# 03_Module.net
KiCad netlist of a schematic drawn in Altium Designer
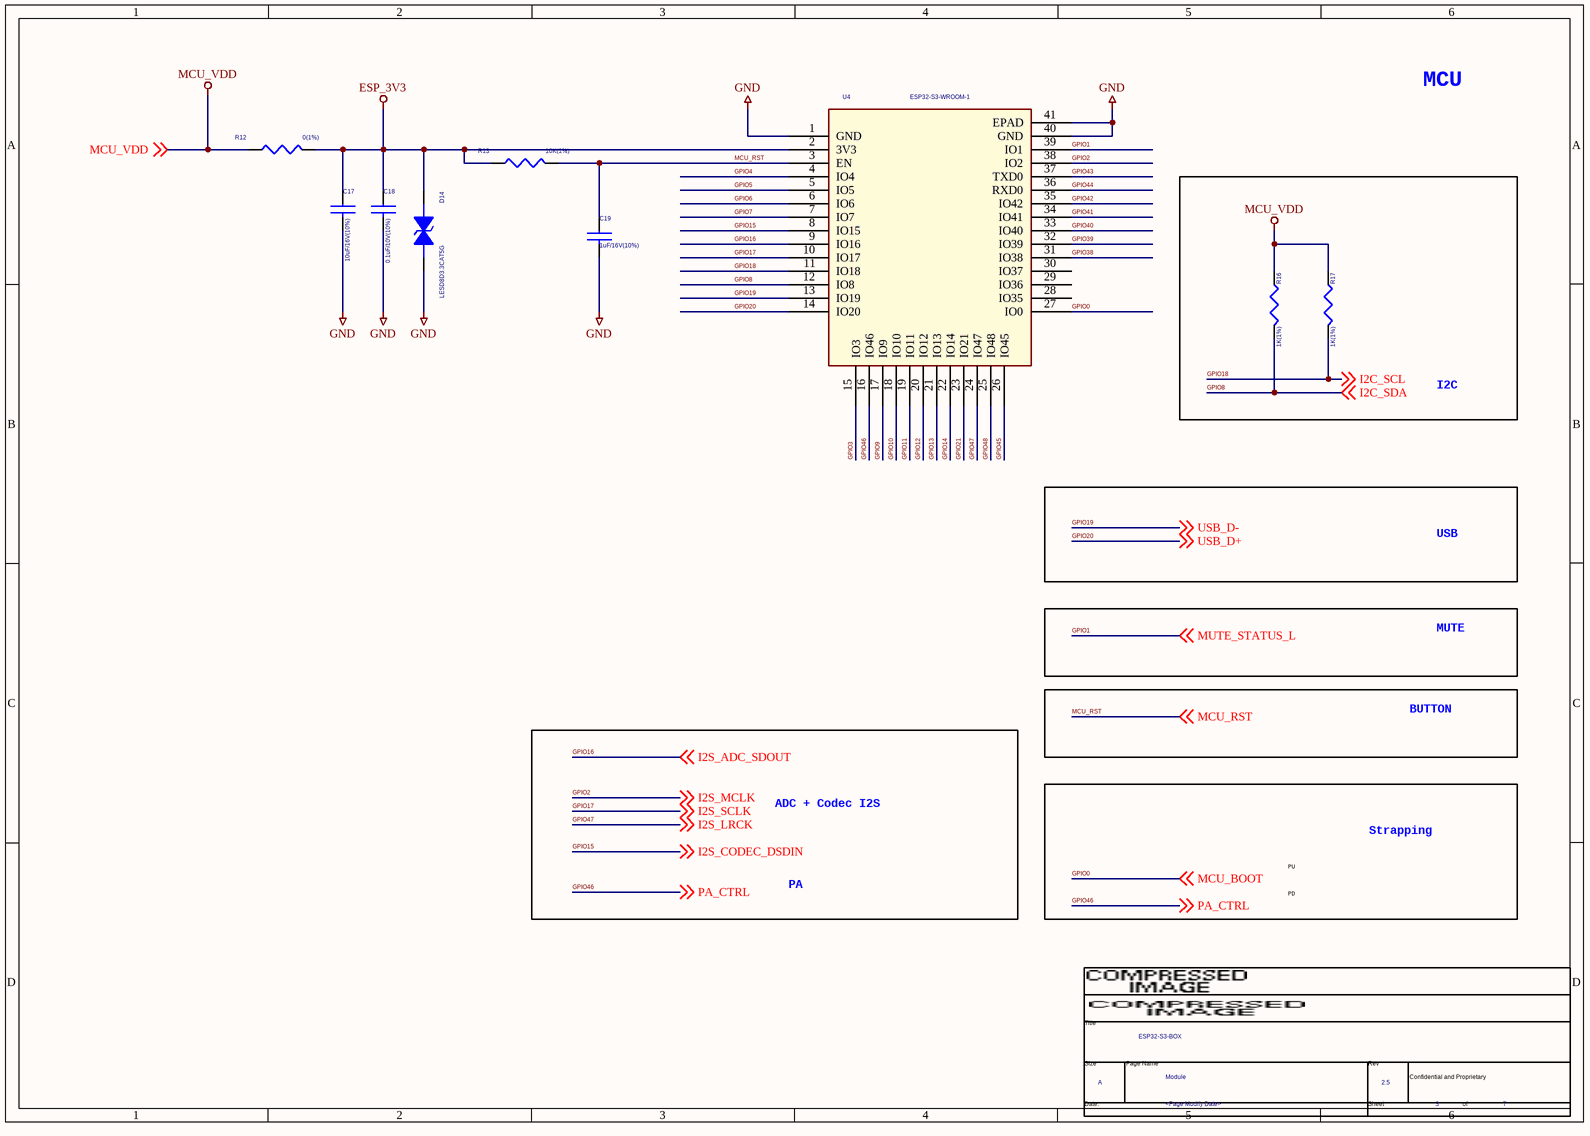
[diagram p0: 03_Module.SchDoc]

(export (version "E")
  (design (tool "Eeschema 10.0.6"))
  (components
    (comp (ref "C17")
      (value "10uF/16V(10%)")
      (footprint "C0603")
      (fields (field (name "PART NUMBER") "ES11067104600000"))
      (libsource (lib "*") (part "CAPACITOR"))
    )
    (comp (ref "C18")
      (value "0.1uF/10V(10%)")
      (footprint "C0402")
      (fields (field (name "PART NUMBER") "ES11045103620000"))
      (libsource (lib "*") (part "CAPACITOR"))
    )
    (comp (ref "C19")
      (value "1uF/16V(10%)")
      (footprint "C0402")
      (fields (field (name "PART NUMBER") "ES11046104610000"))
      (libsource (lib "*") (part "CAPACITOR"))
    )
    (comp (ref "D14")
      (value "LESD8D3.3CAT5G")
      (footprint "SOD882")
      (fields (field (name "PART NUMBER") "ES31320010000000"))
      (libsource (lib "*") (part "DIODE_BI_DIR"))
    )
    (comp (ref "R12")
      (value "0(1%)")
      (footprint "R0603")
      (fields (field (name "PART NUMBER") "ES21060000000001"))
      (libsource (lib "*") (part "RESISTOR"))
    )
    (comp (ref "R13")
      (value "10K(1%)")
      (footprint "R0402")
      (fields (field (name "PART NUMBER") "ES21044100000001"))
      (libsource (lib "*") (part "RESISTOR"))
    )
    (comp (ref "R16")
      (value "1K(1%)")
      (footprint "R0201")
      (fields (field (name "PART NUMBER") "ES21023100000001"))
      (libsource (lib "*") (part "RESISTOR"))
    )
    (comp (ref "R17")
      (value "1K(1%)")
      (footprint "R0201")
      (fields (field (name "PART NUMBER") "ES21023100000001"))
      (libsource (lib "*") (part "RESISTOR"))
    )
    (comp (ref "U4")
      (value "ESP32-S3-WROOM-1")
      (footprint "ESP32-S3-WROOM")
      (libsource (lib "*") (part "ESP32-S3-WROOM"))
    )
  )
  (nets
    (net (code "1") (name "/GPIO3") (class "Default")
      (node (ref "U4") (pin "15") (pinfunction "IO3_15") (pintype "passive"))
    )
    (net (code "2") (name "/GPIO4") (class "Default")
      (node (ref "U4") (pin "4") (pinfunction "IO4_4") (pintype "passive"))
    )
    (net (code "3") (name "/GPIO5") (class "Default")
      (node (ref "U4") (pin "5") (pinfunction "IO5_5") (pintype "passive"))
    )
    (net (code "4") (name "/GPIO6") (class "Default")
      (node (ref "U4") (pin "6") (pinfunction "IO6_6") (pintype "passive"))
    )
    (net (code "5") (name "/GPIO7") (class "Default")
      (node (ref "U4") (pin "7") (pinfunction "IO7_7") (pintype "passive"))
    )
    (net (code "6") (name "/GPIO9") (class "Default")
      (node (ref "U4") (pin "17") (pinfunction "IO9_17") (pintype "passive"))
    )
    (net (code "7") (name "/GPIO10") (class "Default")
      (node (ref "U4") (pin "18") (pinfunction "IO10_18") (pintype "passive"))
    )
    (net (code "8") (name "/GPIO11") (class "Default")
      (node (ref "U4") (pin "19") (pinfunction "IO11_19") (pintype "passive"))
    )
    (net (code "9") (name "/GPIO12") (class "Default")
      (node (ref "U4") (pin "20") (pinfunction "IO12_20") (pintype "passive"))
    )
    (net (code "10") (name "/GPIO13") (class "Default")
      (node (ref "U4") (pin "21") (pinfunction "IO13_21") (pintype "passive"))
    )
    (net (code "11") (name "/GPIO14") (class "Default")
      (node (ref "U4") (pin "22") (pinfunction "IO14_22") (pintype "passive"))
    )
    (net (code "12") (name "/GPIO21") (class "Default")
      (node (ref "U4") (pin "23") (pinfunction "IO21_23") (pintype "passive"))
    )
    (net (code "13") (name "/GPIO38") (class "Default")
      (node (ref "U4") (pin "31") (pinfunction "IO38_31") (pintype "passive"))
    )
    (net (code "14") (name "/GPIO39") (class "Default")
      (node (ref "U4") (pin "32") (pinfunction "IO39_32") (pintype "passive"))
    )
    (net (code "15") (name "/GPIO40") (class "Default")
      (node (ref "U4") (pin "33") (pinfunction "IO40_33") (pintype "passive"))
    )
    (net (code "16") (name "/GPIO41") (class "Default")
      (node (ref "U4") (pin "34") (pinfunction "IO41_34") (pintype "passive"))
    )
    (net (code "17") (name "/GPIO42") (class "Default")
      (node (ref "U4") (pin "35") (pinfunction "IO42_35") (pintype "passive"))
    )
    (net (code "18") (name "/GPIO43") (class "Default")
      (node (ref "U4") (pin "37") (pinfunction "TXD0_37") (pintype "passive"))
    )
    (net (code "19") (name "/GPIO44") (class "Default")
      (node (ref "U4") (pin "36") (pinfunction "RXD0_36") (pintype "passive"))
    )
    (net (code "20") (name "/GPIO45") (class "Default")
      (node (ref "U4") (pin "26") (pinfunction "IO45_26") (pintype "passive"))
    )
    (net (code "21") (name "/GPIO48") (class "Default")
      (node (ref "U4") (pin "25") (pinfunction "IO48_25") (pintype "passive"))
    )
    (net (code "22") (name "ESP_3V3") (class "Default")
      (node (ref "C17") (pin "1") (pinfunction "1_1") (pintype "passive"))
      (node (ref "C18") (pin "1") (pinfunction "1_1") (pintype "passive"))
      (node (ref "D14") (pin "2") (pinfunction "2_2") (pintype "passive"))
      (node (ref "R12") (pin "2") (pinfunction "2_2") (pintype "passive"))
      (node (ref "R13") (pin "1") (pinfunction "1_1") (pintype "passive"))
      (node (ref "U4") (pin "2") (pinfunction "3V3_2") (pintype "power_in"))
    )
    (net (code "23") (name "GND") (class "Default")
      (node (ref "C17") (pin "2") (pinfunction "2_2") (pintype "passive"))
      (node (ref "C18") (pin "2") (pinfunction "2_2") (pintype "passive"))
      (node (ref "C19") (pin "2") (pinfunction "2_2") (pintype "passive"))
      (node (ref "D14") (pin "1") (pinfunction "1_1") (pintype "passive"))
      (node (ref "U4") (pin "1") (pinfunction "GND_1") (pintype "power_in"))
      (node (ref "U4") (pin "40") (pinfunction "GND_40") (pintype "power_in"))
      (node (ref "U4") (pin "41") (pinfunction "EPAD_41") (pintype "power_in"))
    )
    (net (code "24") (name "I2C_SCL") (class "Default")
      (node (ref "R17") (pin "2") (pinfunction "2_2") (pintype "passive"))
      (node (ref "U4") (pin "11") (pinfunction "IO18_11") (pintype "passive"))
    )
    (net (code "25") (name "I2C_SDA") (class "Default")
      (node (ref "R16") (pin "2") (pinfunction "2_2") (pintype "passive"))
      (node (ref "U4") (pin "12") (pinfunction "IO8_12") (pintype "passive"))
    )
    (net (code "26") (name "I2S_ADC_SDOUT") (class "Default")
      (node (ref "U4") (pin "9") (pinfunction "IO16_9") (pintype "passive"))
    )
    (net (code "27") (name "I2S_CODEC_DSDIN") (class "Default")
      (node (ref "U4") (pin "8") (pinfunction "IO15_8") (pintype "passive"))
    )
    (net (code "28") (name "I2S_LRCK") (class "Default")
      (node (ref "U4") (pin "24") (pinfunction "IO47_24") (pintype "passive"))
    )
    (net (code "29") (name "I2S_MCLK") (class "Default")
      (node (ref "U4") (pin "38") (pinfunction "IO2_38") (pintype "passive"))
    )
    (net (code "30") (name "I2S_SCLK") (class "Default")
      (node (ref "U4") (pin "10") (pinfunction "IO17_10") (pintype "passive"))
    )
    (net (code "31") (name "MCU_BOOT") (class "Default")
      (node (ref "U4") (pin "27") (pinfunction "IO0_27") (pintype "passive"))
    )
    (net (code "32") (name "MCU_RST") (class "Default")
      (node (ref "C19") (pin "1") (pinfunction "1_1") (pintype "passive"))
      (node (ref "R13") (pin "2") (pinfunction "2_2") (pintype "passive"))
      (node (ref "U4") (pin "3") (pinfunction "EN_3") (pintype "passive"))
    )
    (net (code "33") (name "MCU_VDD") (class "Default")
      (node (ref "R12") (pin "1") (pinfunction "1_1") (pintype "passive"))
      (node (ref "R16") (pin "1") (pinfunction "1_1") (pintype "passive"))
      (node (ref "R17") (pin "1") (pinfunction "1_1") (pintype "passive"))
    )
    (net (code "34") (name "MUTE_STATUS_L") (class "Default")
      (node (ref "U4") (pin "39") (pinfunction "IO1_39") (pintype "passive"))
    )
    (net (code "35") (name "PA_CTRL") (class "Default")
      (node (ref "U4") (pin "16") (pinfunction "IO46_16") (pintype "passive"))
    )
    (net (code "36") (name "USB_D+") (class "Default")
      (node (ref "U4") (pin "14") (pinfunction "IO20_14") (pintype "passive"))
    )
    (net (code "37") (name "USB_D-") (class "Default")
      (node (ref "U4") (pin "13") (pinfunction "IO19_13") (pintype "passive"))
    )
    (net (code "38") (name "unconnected-(U4-IO35-Pad28)") (class "Default")
      (node (ref "U4") (pin "28") (pinfunction "IO35_28") (pintype "passive"))
    )
    (net (code "39") (name "unconnected-(U4-IO36-Pad29)") (class "Default")
      (node (ref "U4") (pin "29") (pinfunction "IO36_29") (pintype "passive"))
    )
    (net (code "40") (name "unconnected-(U4-IO37-Pad30)") (class "Default")
      (node (ref "U4") (pin "30") (pinfunction "IO37_30") (pintype "passive"))
    )
  )
)
